# SCH_R2D2_2024-01-11.net
KiCad netlist of a schematic drawn in EasyEDA
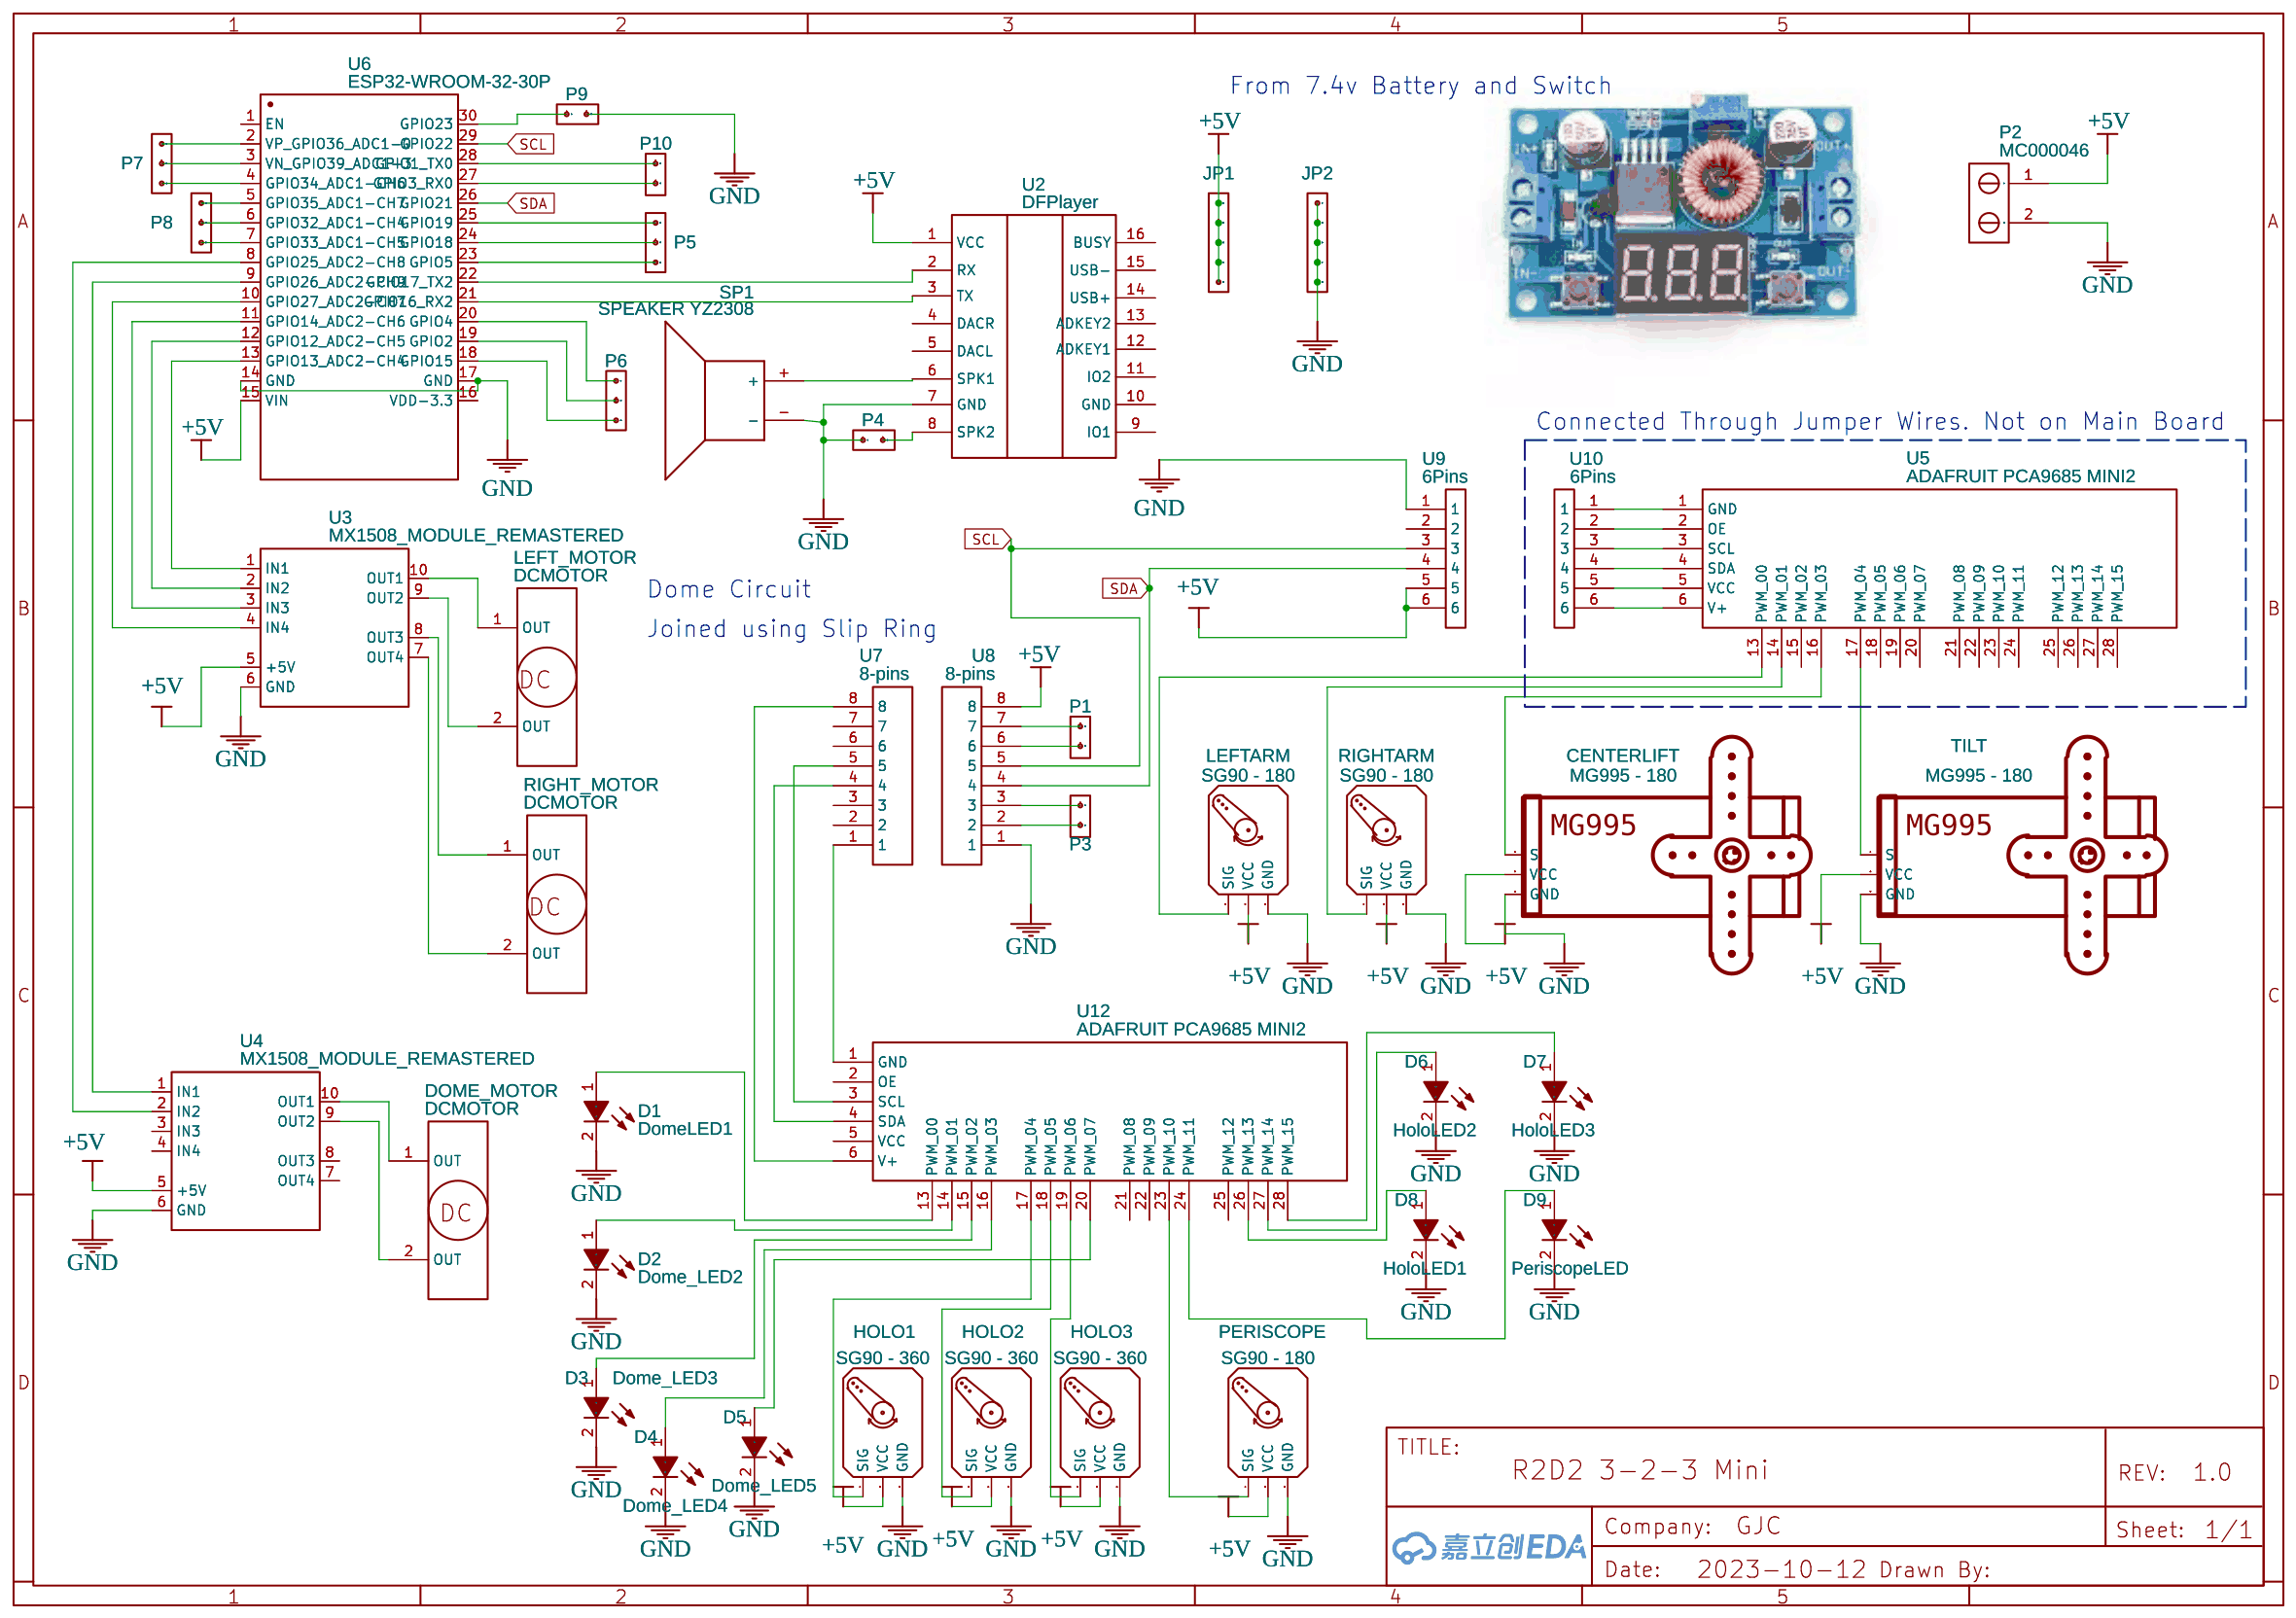
[diagram p0: schematic sheet]

(export (version "E")
  (design (tool "Eeschema 10.0.6"))
  (components
    (comp (ref "CENTERLIFT") (value "MG995 - 180") (libsource (lib "") (part "Servomotor_MG995_1")))
    (comp (ref "D1")
      (value "DomeLED1")
      (fields (field (name "Manufacturer Part") "5600") (field (name "Manufacturer") "VccLite"))
      (libsource (lib "") (part "3mm Green TH LED 5600"))
    )
    (comp (ref "D2")
      (value "Dome_LED2")
      (fields (field (name "Manufacturer Part") "5600") (field (name "Manufacturer") "VccLite"))
      (libsource (lib "") (part "3mm Green TH LED 5600"))
    )
    (comp (ref "D3")
      (value "Dome_LED3")
      (fields (field (name "Manufacturer Part") "5600") (field (name "Manufacturer") "VccLite"))
      (libsource (lib "") (part "3mm Green TH LED 5600"))
    )
    (comp (ref "D4")
      (value "Dome_LED4")
      (fields (field (name "Manufacturer Part") "5600") (field (name "Manufacturer") "VccLite"))
      (libsource (lib "") (part "3mm Green TH LED 5600"))
    )
    (comp (ref "D5")
      (value "Dome_LED5")
      (fields (field (name "Manufacturer Part") "5600") (field (name "Manufacturer") "VccLite"))
      (libsource (lib "") (part "3mm Green TH LED 5600"))
    )
    (comp (ref "D6")
      (value "HoloLED2")
      (fields (field (name "Manufacturer Part") "5600") (field (name "Manufacturer") "VccLite"))
      (libsource (lib "") (part "3mm Green TH LED 5600"))
    )
    (comp (ref "D7")
      (value "HoloLED3")
      (fields (field (name "Manufacturer Part") "5600") (field (name "Manufacturer") "VccLite"))
      (libsource (lib "") (part "3mm Green TH LED 5600"))
    )
    (comp (ref "D8")
      (value "HoloLED1")
      (fields (field (name "Manufacturer Part") "5600") (field (name "Manufacturer") "VccLite"))
      (libsource (lib "") (part "3mm Green TH LED 5600"))
    )
    (comp (ref "D9")
      (value "PeriscopeLED")
      (fields (field (name "Manufacturer Part") "5600") (field (name "Manufacturer") "VccLite"))
      (libsource (lib "") (part "3mm Green TH LED 5600"))
    )
    (comp (ref "DOME_MOTOR") (value "DCMOTOR") (libsource (lib "") (part "DCMOTOR_2")))
    (comp (ref "HOLO1") (value "SG90 - 360") (libsource (lib "") (part "SG90_Servo")))
    (comp (ref "HOLO2") (value "SG90 - 360") (libsource (lib "") (part "SG90_Servo")))
    (comp (ref "HOLO3") (value "SG90 - 360") (libsource (lib "") (part "SG90_Servo")))
    (comp (ref "JP1") (value "1X5PIN") (libsource (lib "") (part "1X5PIN")))
    (comp (ref "JP2") (value "1X5PIN") (libsource (lib "") (part "1X5PIN")))
    (comp (ref "LEFTARM") (value "SG90 - 180") (libsource (lib "") (part "SG90_Servo_2")))
    (comp (ref "LEFT_MOTOR") (value "DCMOTOR") (libsource (lib "") (part "DCMOTOR_1")))
    (comp (ref "P1") (value "1X2PIN") (libsource (lib "") (part "1X2PIN")))
    (comp (ref "P2")
      (value "MC000046")
      (fields (field (name "BOM_Supplier Part") "2008017"))
      (libsource (lib "") (part "MC000046"))
    )
    (comp (ref "P3") (value "1X2PIN") (libsource (lib "") (part "1X2PIN")))
    (comp (ref "P4") (value "1X2PIN") (libsource (lib "") (part "1X2PIN_1")))
    (comp (ref "P5") (value "1X3PIN") (libsource (lib "") (part "1X3PIN")))
    (comp (ref "P6") (value "1X3PIN") (libsource (lib "") (part "1X3PIN")))
    (comp (ref "P7") (value "1X3PIN") (libsource (lib "") (part "1X3PIN")))
    (comp (ref "P8") (value "1X3PIN") (libsource (lib "") (part "1X3PIN")))
    (comp (ref "P9") (value "1X2PIN") (libsource (lib "") (part "1X2PIN_1")))
    (comp (ref "P10") (value "1X2PIN") (libsource (lib "") (part "1X2PIN")))
    (comp (ref "PERISCOPE") (value "SG90 - 180") (libsource (lib "") (part "SG90_Servo_3")))
    (comp (ref "RIGHTARM") (value "SG90 - 180") (libsource (lib "") (part "SG90_Servo_1")))
    (comp (ref "RIGHT_MOTOR") (value "DCMOTOR") (libsource (lib "") (part "DCMOTOR")))
    (comp (ref "SP1")
      (value "SPEAKER YZ2308")
      (fields (field (name "BOM_Manufacturer Part") "YZ2308"))
      (libsource (lib "") (part "SPEAKER YZ2308"))
    )
    (comp (ref "TILT") (value "MG995 - 180") (libsource (lib "") (part "Servomotor_MG995")))
    (comp (ref "U2") (value "DFPlayer") (libsource (lib "") (part "DFPlayer")))
    (comp (ref "U3")
      (value "MX1508_MODULE_REMASTERED")
      (libsource (lib "") (part "MX1508_MODULE_REMASTERED"))
    )
    (comp (ref "U4")
      (value "MX1508_MODULE_REMASTERED")
      (libsource (lib "") (part "MX1508_MODULE_REMASTERED"))
    )
    (comp (ref "U5") (value "ADAFRUIT PCA9685 MINI2") (libsource (lib "") (part "ADAFRUIT PCA9685 MINI2")))
    (comp (ref "U6")
      (value "ESP32-WROOM-32-30P")
      (fields (field (name "BOM_Supplier Part") "C82899"))
      (libsource (lib "") (part "ESP32-WROOM-32-30P"))
    )
    (comp (ref "U7") (value "8-pins") (libsource (lib "") (part "8-pins_1")))
    (comp (ref "U8") (value "8-pins") (libsource (lib "") (part "8-pins")))
    (comp (ref "U9") (value "6Pins") (libsource (lib "") (part "6Pins_1")))
    (comp (ref "U10") (value "6Pins") (libsource (lib "") (part "6Pins")))
    (comp (ref "U12") (value "ADAFRUIT PCA9685 MINI2") (libsource (lib "") (part "ADAFRUIT PCA9685 MINI2")))
  )
  (nets
    (net (code "1") (name "+5V") (class "Default")
      (node (ref "CENTERLIFT") (pin "2") (pinfunction "VCC_2") (pintype "unspecified"))
      (node (ref "HOLO1") (pin "2") (pinfunction "VCC_2") (pintype "unspecified"))
      (node (ref "HOLO2") (pin "2") (pinfunction "VCC_2") (pintype "unspecified"))
      (node (ref "HOLO3") (pin "2") (pinfunction "VCC_2") (pintype "unspecified"))
      (node (ref "JP1") (pin "1") (pinfunction "1_1") (pintype "unspecified"))
      (node (ref "JP1") (pin "2") (pinfunction "2_2") (pintype "unspecified"))
      (node (ref "JP1") (pin "3") (pinfunction "3_3") (pintype "unspecified"))
      (node (ref "JP1") (pin "4") (pinfunction "4_4") (pintype "unspecified"))
      (node (ref "JP1") (pin "5") (pinfunction "5_5") (pintype "unspecified"))
      (node (ref "LEFTARM") (pin "2") (pinfunction "VCC_2") (pintype "unspecified"))
      (node (ref "P2") (pin "1") (pinfunction "1_1") (pintype "input"))
      (node (ref "PERISCOPE") (pin "2") (pinfunction "VCC_2") (pintype "unspecified"))
      (node (ref "RIGHTARM") (pin "2") (pinfunction "VCC_2") (pintype "unspecified"))
      (node (ref "TILT") (pin "2") (pinfunction "VCC_2") (pintype "unspecified"))
      (node (ref "U2") (pin "1") (pinfunction "VCC_1") (pintype "unspecified"))
      (node (ref "U3") (pin "5") (pinfunction "+5V_5") (pintype "unspecified"))
      (node (ref "U4") (pin "5") (pinfunction "+5V_5") (pintype "unspecified"))
      (node (ref "U6") (pin "15") (pinfunction "VIN_15") (pintype "unspecified"))
      (node (ref "U8") (pin "8") (pinfunction "8_8") (pintype "unspecified"))
      (node (ref "U9") (pin "5") (pinfunction "5_5") (pintype "unspecified"))
      (node (ref "U9") (pin "6") (pinfunction "6_6") (pintype "unspecified"))
    )
    (net (code "2") (name "GND") (class "Default")
      (node (ref "CENTERLIFT") (pin "3") (pinfunction "GND_3") (pintype "unspecified"))
      (node (ref "D1") (pin "2") (pinfunction "K_2") (pintype "unspecified"))
      (node (ref "D2") (pin "2") (pinfunction "K_2") (pintype "unspecified"))
      (node (ref "D3") (pin "2") (pinfunction "K_2") (pintype "unspecified"))
      (node (ref "D4") (pin "2") (pinfunction "K_2") (pintype "unspecified"))
      (node (ref "D5") (pin "2") (pinfunction "K_2") (pintype "unspecified"))
      (node (ref "D6") (pin "2") (pinfunction "K_2") (pintype "unspecified"))
      (node (ref "D7") (pin "2") (pinfunction "K_2") (pintype "unspecified"))
      (node (ref "D8") (pin "2") (pinfunction "K_2") (pintype "unspecified"))
      (node (ref "D9") (pin "2") (pinfunction "K_2") (pintype "unspecified"))
      (node (ref "HOLO1") (pin "3") (pinfunction "GND_3") (pintype "unspecified"))
      (node (ref "HOLO2") (pin "3") (pinfunction "GND_3") (pintype "unspecified"))
      (node (ref "HOLO3") (pin "3") (pinfunction "GND_3") (pintype "unspecified"))
      (node (ref "JP2") (pin "1") (pinfunction "1_1") (pintype "unspecified"))
      (node (ref "JP2") (pin "2") (pinfunction "2_2") (pintype "unspecified"))
      (node (ref "JP2") (pin "3") (pinfunction "3_3") (pintype "unspecified"))
      (node (ref "JP2") (pin "4") (pinfunction "4_4") (pintype "unspecified"))
      (node (ref "JP2") (pin "5") (pinfunction "5_5") (pintype "unspecified"))
      (node (ref "LEFTARM") (pin "3") (pinfunction "GND_3") (pintype "unspecified"))
      (node (ref "P2") (pin "2") (pinfunction "2_2") (pintype "input"))
      (node (ref "P4") (pin "1") (pinfunction "1_1") (pintype "unspecified"))
      (node (ref "P9") (pin "2") (pinfunction "2_2") (pintype "unspecified"))
      (node (ref "PERISCOPE") (pin "3") (pinfunction "GND_3") (pintype "unspecified"))
      (node (ref "RIGHTARM") (pin "3") (pinfunction "GND_3") (pintype "unspecified"))
      (node (ref "SP1") (pin "-") (pinfunction "-_-") (pintype "unspecified"))
      (node (ref "TILT") (pin "3") (pinfunction "GND_3") (pintype "unspecified"))
      (node (ref "U2") (pin "7") (pinfunction "GND_7") (pintype "unspecified"))
      (node (ref "U3") (pin "6") (pinfunction "GND_6") (pintype "unspecified"))
      (node (ref "U4") (pin "6") (pinfunction "GND_6") (pintype "unspecified"))
      (node (ref "U6") (pin "14") (pinfunction "GND_14") (pintype "unspecified"))
      (node (ref "U6") (pin "17") (pinfunction "GND_17") (pintype "unspecified"))
      (node (ref "U8") (pin "1") (pinfunction "1_1") (pintype "unspecified"))
      (node (ref "U9") (pin "1") (pinfunction "1_1") (pintype "unspecified"))
    )
    (net (code "3") (name "Net-(CENTERLIFT-S)") (class "Default")
      (node (ref "CENTERLIFT") (pin "1") (pinfunction "S_1") (pintype "unspecified"))
      (node (ref "U5") (pin "16") (pinfunction "PWM_03_16") (pintype "unspecified"))
    )
    (net (code "4") (name "Net-(D1-A)") (class "Default")
      (node (ref "D1") (pin "1") (pinfunction "A_1") (pintype "unspecified"))
      (node (ref "U12") (pin "13") (pinfunction "PWM_00_13") (pintype "unspecified"))
    )
    (net (code "5") (name "Net-(D2-A)") (class "Default")
      (node (ref "D2") (pin "1") (pinfunction "A_1") (pintype "unspecified"))
      (node (ref "U12") (pin "14") (pinfunction "PWM_01_14") (pintype "unspecified"))
    )
    (net (code "6") (name "Net-(D3-A)") (class "Default")
      (node (ref "D3") (pin "1") (pinfunction "A_1") (pintype "unspecified"))
      (node (ref "U12") (pin "15") (pinfunction "PWM_02_15") (pintype "unspecified"))
    )
    (net (code "7") (name "Net-(D4-A)") (class "Default")
      (node (ref "D4") (pin "1") (pinfunction "A_1") (pintype "unspecified"))
      (node (ref "U12") (pin "16") (pinfunction "PWM_03_16") (pintype "unspecified"))
    )
    (net (code "8") (name "Net-(D5-A)") (class "Default")
      (node (ref "D5") (pin "1") (pinfunction "A_1") (pintype "unspecified"))
      (node (ref "U12") (pin "20") (pinfunction "PWM_07_20") (pintype "unspecified"))
    )
    (net (code "9") (name "Net-(D6-A)") (class "Default")
      (node (ref "D6") (pin "1") (pinfunction "A_1") (pintype "unspecified"))
      (node (ref "U12") (pin "27") (pinfunction "PWM_14_27") (pintype "unspecified"))
    )
    (net (code "10") (name "Net-(D7-A)") (class "Default")
      (node (ref "D7") (pin "1") (pinfunction "A_1") (pintype "unspecified"))
      (node (ref "U12") (pin "28") (pinfunction "PWM_15_28") (pintype "unspecified"))
    )
    (net (code "11") (name "Net-(D8-A)") (class "Default")
      (node (ref "D8") (pin "1") (pinfunction "A_1") (pintype "unspecified"))
      (node (ref "U12") (pin "26") (pinfunction "PWM_13_26") (pintype "unspecified"))
    )
    (net (code "12") (name "Net-(D9-A)") (class "Default")
      (node (ref "D9") (pin "1") (pinfunction "A_1") (pintype "unspecified"))
      (node (ref "U12") (pin "24") (pinfunction "PWM_11_24") (pintype "unspecified"))
    )
    (net (code "13") (name "Net-(HOLO1-SIG)") (class "Default")
      (node (ref "HOLO1") (pin "1") (pinfunction "SIG_1") (pintype "unspecified"))
      (node (ref "U12") (pin "17") (pinfunction "PWM_04_17") (pintype "unspecified"))
    )
    (net (code "14") (name "Net-(HOLO2-SIG)") (class "Default")
      (node (ref "HOLO2") (pin "1") (pinfunction "SIG_1") (pintype "unspecified"))
      (node (ref "U12") (pin "18") (pinfunction "PWM_05_18") (pintype "unspecified"))
    )
    (net (code "15") (name "Net-(HOLO3-SIG)") (class "Default")
      (node (ref "HOLO3") (pin "1") (pinfunction "SIG_1") (pintype "unspecified"))
      (node (ref "U12") (pin "19") (pinfunction "PWM_06_19") (pintype "unspecified"))
    )
    (net (code "16") (name "Net-(LEFTARM-SIG)") (class "Default")
      (node (ref "LEFTARM") (pin "1") (pinfunction "SIG_1") (pintype "unspecified"))
      (node (ref "U5") (pin "13") (pinfunction "PWM_00_13") (pintype "unspecified"))
    )
    (net (code "17") (name "Net-(P1-Pad1)") (class "Default")
      (node (ref "P1") (pin "1") (pinfunction "1_1") (pintype "unspecified"))
      (node (ref "U8") (pin "7") (pinfunction "7_7") (pintype "unspecified"))
    )
    (net (code "18") (name "Net-(P1-Pad2)") (class "Default")
      (node (ref "P1") (pin "2") (pinfunction "2_2") (pintype "unspecified"))
      (node (ref "U8") (pin "6") (pinfunction "6_6") (pintype "unspecified"))
    )
    (net (code "19") (name "Net-(P3-Pad1)") (class "Default")
      (node (ref "P3") (pin "1") (pinfunction "1_1") (pintype "unspecified"))
      (node (ref "U8") (pin "3") (pinfunction "3_3") (pintype "unspecified"))
    )
    (net (code "20") (name "Net-(P3-Pad2)") (class "Default")
      (node (ref "P3") (pin "2") (pinfunction "2_2") (pintype "unspecified"))
      (node (ref "U8") (pin "2") (pinfunction "2_2") (pintype "unspecified"))
    )
    (net (code "21") (name "Net-(PERISCOPE-SIG)") (class "Default")
      (node (ref "PERISCOPE") (pin "1") (pinfunction "SIG_1") (pintype "unspecified"))
      (node (ref "U12") (pin "23") (pinfunction "PWM_10_23") (pintype "unspecified"))
    )
    (net (code "22") (name "Net-(RIGHTARM-SIG)") (class "Default")
      (node (ref "RIGHTARM") (pin "1") (pinfunction "SIG_1") (pintype "unspecified"))
      (node (ref "U5") (pin "14") (pinfunction "PWM_01_14") (pintype "unspecified"))
    )
    (net (code "23") (name "Net-(TILT-S)") (class "Default")
      (node (ref "TILT") (pin "1") (pinfunction "S_1") (pintype "unspecified"))
      (node (ref "U5") (pin "17") (pinfunction "PWM_04_17") (pintype "unspecified"))
    )
    (net (code "24") (name "Net-(U2-RX)") (class "Default")
      (node (ref "U2") (pin "2") (pinfunction "RX_2") (pintype "unspecified"))
      (node (ref "U6") (pin "22") (pinfunction "GPIO17_TX2_22") (pintype "unspecified"))
    )
    (net (code "25") (name "Net-(U2-SPK1)") (class "Default")
      (node (ref "SP1") (pin "+") (pinfunction "+_+") (pintype "unspecified"))
      (node (ref "U2") (pin "6") (pinfunction "SPK1_6") (pintype "unspecified"))
    )
    (net (code "26") (name "Net-(U2-SPK2)") (class "Default")
      (node (ref "P4") (pin "2") (pinfunction "2_2") (pintype "unspecified"))
      (node (ref "U2") (pin "8") (pinfunction "SPK2_8") (pintype "unspecified"))
    )
    (net (code "27") (name "Net-(U2-TX)") (class "Default")
      (node (ref "U2") (pin "3") (pinfunction "TX_3") (pintype "unspecified"))
      (node (ref "U6") (pin "21") (pinfunction "GPIO16_RX2_21") (pintype "unspecified"))
    )
    (net (code "28") (name "Net-(U3-IN1)") (class "Default")
      (node (ref "U3") (pin "1") (pinfunction "IN1_1") (pintype "unspecified"))
      (node (ref "U6") (pin "13") (pinfunction "GPIO13_ADC2-CH4_13") (pintype "unspecified"))
    )
    (net (code "29") (name "Net-(U3-IN2)") (class "Default")
      (node (ref "U3") (pin "2") (pinfunction "IN2_2") (pintype "unspecified"))
      (node (ref "U6") (pin "12") (pinfunction "GPIO12_ADC2-CH5_12") (pintype "unspecified"))
    )
    (net (code "30") (name "Net-(U3-IN3)") (class "Default")
      (node (ref "U3") (pin "3") (pinfunction "IN3_3") (pintype "unspecified"))
      (node (ref "U6") (pin "11") (pinfunction "GPIO14_ADC2-CH6_11") (pintype "unspecified"))
    )
    (net (code "31") (name "Net-(U3-IN4)") (class "Default")
      (node (ref "U3") (pin "4") (pinfunction "IN4_4") (pintype "unspecified"))
      (node (ref "U6") (pin "10") (pinfunction "GPIO27_ADC2-CH7_10") (pintype "unspecified"))
    )
    (net (code "32") (name "Net-(U3-OUT1)") (class "Default")
      (node (ref "LEFT_MOTOR") (pin "1") (pinfunction "OUT_1") (pintype "unspecified"))
      (node (ref "U3") (pin "10") (pinfunction "OUT1_10") (pintype "unspecified"))
    )
    (net (code "33") (name "Net-(U3-OUT2)") (class "Default")
      (node (ref "LEFT_MOTOR") (pin "2") (pinfunction "OUT_2") (pintype "unspecified"))
      (node (ref "U3") (pin "9") (pinfunction "OUT2_9") (pintype "unspecified"))
    )
    (net (code "34") (name "Net-(U3-OUT3)") (class "Default")
      (node (ref "RIGHT_MOTOR") (pin "1") (pinfunction "OUT_1") (pintype "unspecified"))
      (node (ref "U3") (pin "8") (pinfunction "OUT3_8") (pintype "unspecified"))
    )
    (net (code "35") (name "Net-(U3-OUT4)") (class "Default")
      (node (ref "RIGHT_MOTOR") (pin "2") (pinfunction "OUT_2") (pintype "unspecified"))
      (node (ref "U3") (pin "7") (pinfunction "OUT4_7") (pintype "unspecified"))
    )
    (net (code "36") (name "Net-(U4-IN1)") (class "Default")
      (node (ref "U4") (pin "1") (pinfunction "IN1_1") (pintype "unspecified"))
      (node (ref "U6") (pin "9") (pinfunction "GPIO26_ADC2-CH9_9") (pintype "unspecified"))
    )
    (net (code "37") (name "Net-(U4-IN2)") (class "Default")
      (node (ref "U4") (pin "2") (pinfunction "IN2_2") (pintype "unspecified"))
      (node (ref "U6") (pin "8") (pinfunction "GPIO25_ADC2-CH8_8") (pintype "unspecified"))
    )
    (net (code "38") (name "Net-(U4-OUT1)") (class "Default")
      (node (ref "DOME_MOTOR") (pin "1") (pinfunction "OUT_1") (pintype "unspecified"))
      (node (ref "U4") (pin "10") (pinfunction "OUT1_10") (pintype "unspecified"))
    )
    (net (code "39") (name "Net-(U4-OUT2)") (class "Default")
      (node (ref "DOME_MOTOR") (pin "2") (pinfunction "OUT_2") (pintype "unspecified"))
      (node (ref "U4") (pin "9") (pinfunction "OUT2_9") (pintype "unspecified"))
    )
    (net (code "40") (name "Net-(U5-GND)") (class "Default")
      (node (ref "U10") (pin "1") (pinfunction "1_1") (pintype "unspecified"))
      (node (ref "U5") (pin "1") (pinfunction "GND_1") (pintype "unspecified"))
    )
    (net (code "41") (name "Net-(U5-OE)") (class "Default")
      (node (ref "U10") (pin "2") (pinfunction "2_2") (pintype "unspecified"))
      (node (ref "U5") (pin "2") (pinfunction "OE_2") (pintype "unspecified"))
    )
    (net (code "42") (name "Net-(U5-SCL)") (class "Default")
      (node (ref "U10") (pin "3") (pinfunction "3_3") (pintype "unspecified"))
      (node (ref "U5") (pin "3") (pinfunction "SCL_3") (pintype "unspecified"))
    )
    (net (code "43") (name "Net-(U5-SDA)") (class "Default")
      (node (ref "U10") (pin "4") (pinfunction "4_4") (pintype "unspecified"))
      (node (ref "U5") (pin "4") (pinfunction "SDA_4") (pintype "unspecified"))
    )
    (net (code "44") (name "Net-(U5-V+)") (class "Default")
      (node (ref "U10") (pin "6") (pinfunction "6_6") (pintype "unspecified"))
      (node (ref "U5") (pin "6") (pinfunction "V+_6") (pintype "unspecified"))
    )
    (net (code "45") (name "Net-(U5-VCC)") (class "Default")
      (node (ref "U10") (pin "5") (pinfunction "5_5") (pintype "unspecified"))
      (node (ref "U5") (pin "5") (pinfunction "VCC_5") (pintype "unspecified"))
    )
    (net (code "46") (name "Net-(U6-GPIO1_TX0)") (class "Default")
      (node (ref "P10") (pin "1") (pinfunction "1_1") (pintype "unspecified"))
      (node (ref "U6") (pin "28") (pinfunction "GPIO1_TX0_28") (pintype "unspecified"))
    )
    (net (code "47") (name "Net-(U6-GPIO2)") (class "Default")
      (node (ref "P6") (pin "2") (pinfunction "2_2") (pintype "unspecified"))
      (node (ref "U6") (pin "19") (pinfunction "GPIO2_19") (pintype "unspecified"))
    )
    (net (code "48") (name "Net-(U6-GPIO3_RX0)") (class "Default")
      (node (ref "P10") (pin "2") (pinfunction "2_2") (pintype "unspecified"))
      (node (ref "U6") (pin "27") (pinfunction "GPIO3_RX0_27") (pintype "unspecified"))
    )
    (net (code "49") (name "Net-(U6-GPIO4)") (class "Default")
      (node (ref "P6") (pin "1") (pinfunction "1_1") (pintype "unspecified"))
      (node (ref "U6") (pin "20") (pinfunction "GPIO4_20") (pintype "unspecified"))
    )
    (net (code "50") (name "Net-(U6-GPIO5)") (class "Default")
      (node (ref "P5") (pin "3") (pinfunction "3_3") (pintype "unspecified"))
      (node (ref "U6") (pin "23") (pinfunction "GPIO5_23") (pintype "unspecified"))
    )
    (net (code "51") (name "Net-(U6-GPIO15)") (class "Default")
      (node (ref "P6") (pin "3") (pinfunction "3_3") (pintype "unspecified"))
      (node (ref "U6") (pin "18") (pinfunction "GPIO15_18") (pintype "unspecified"))
    )
    (net (code "52") (name "Net-(U6-GPIO18)") (class "Default")
      (node (ref "P5") (pin "2") (pinfunction "2_2") (pintype "unspecified"))
      (node (ref "U6") (pin "24") (pinfunction "GPIO18_24") (pintype "unspecified"))
    )
    (net (code "53") (name "Net-(U6-GPIO19)") (class "Default")
      (node (ref "P5") (pin "1") (pinfunction "1_1") (pintype "unspecified"))
      (node (ref "U6") (pin "25") (pinfunction "GPIO19_25") (pintype "unspecified"))
    )
    (net (code "54") (name "Net-(U6-GPIO23)") (class "Default")
      (node (ref "P9") (pin "1") (pinfunction "1_1") (pintype "unspecified"))
      (node (ref "U6") (pin "30") (pinfunction "GPIO23_30") (pintype "unspecified"))
    )
    (net (code "55") (name "Net-(U6-GPIO32_ADC1-CH4)") (class "Default")
      (node (ref "P8") (pin "2") (pinfunction "2_2") (pintype "unspecified"))
      (node (ref "U6") (pin "6") (pinfunction "GPIO32_ADC1-CH4_6") (pintype "unspecified"))
    )
    (net (code "56") (name "Net-(U6-GPIO33_ADC1-CH5)") (class "Default")
      (node (ref "P8") (pin "3") (pinfunction "3_3") (pintype "unspecified"))
      (node (ref "U6") (pin "7") (pinfunction "GPIO33_ADC1-CH5_7") (pintype "unspecified"))
    )
    (net (code "57") (name "Net-(U6-GPIO34_ADC1-CH6)") (class "Default")
      (node (ref "P7") (pin "3") (pinfunction "3_3") (pintype "unspecified"))
      (node (ref "U6") (pin "4") (pinfunction "GPIO34_ADC1-CH6_4") (pintype "unspecified"))
    )
    (net (code "58") (name "Net-(U6-GPIO35_ADC1-CH7)") (class "Default")
      (node (ref "P8") (pin "1") (pinfunction "1_1") (pintype "unspecified"))
      (node (ref "U6") (pin "5") (pinfunction "GPIO35_ADC1-CH7_5") (pintype "unspecified"))
    )
    (net (code "59") (name "Net-(U6-VN_GPIO39_ADC1-3)") (class "Default")
      (node (ref "P7") (pin "2") (pinfunction "2_2") (pintype "unspecified"))
      (node (ref "U6") (pin "3") (pinfunction "VN_GPIO39_ADC1-3_3") (pintype "unspecified"))
    )
    (net (code "60") (name "Net-(U6-VP_GPIO36_ADC1-0)") (class "Default")
      (node (ref "P7") (pin "1") (pinfunction "1_1") (pintype "unspecified"))
      (node (ref "U6") (pin "2") (pinfunction "VP_GPIO36_ADC1-0_2") (pintype "unspecified"))
    )
    (net (code "61") (name "Net-(U12-GND)") (class "Default")
      (node (ref "U12") (pin "1") (pinfunction "GND_1") (pintype "unspecified"))
      (node (ref "U7") (pin "1") (pinfunction "1_1") (pintype "unspecified"))
    )
    (net (code "62") (name "Net-(U12-SCL)") (class "Default")
      (node (ref "U12") (pin "3") (pinfunction "SCL_3") (pintype "unspecified"))
      (node (ref "U7") (pin "5") (pinfunction "5_5") (pintype "unspecified"))
    )
    (net (code "63") (name "Net-(U12-SDA)") (class "Default")
      (node (ref "U12") (pin "4") (pinfunction "SDA_4") (pintype "unspecified"))
      (node (ref "U7") (pin "4") (pinfunction "4_4") (pintype "unspecified"))
    )
    (net (code "64") (name "Net-(U12-V+)") (class "Default")
      (node (ref "U12") (pin "6") (pinfunction "V+_6") (pintype "unspecified"))
      (node (ref "U7") (pin "8") (pinfunction "8_8") (pintype "unspecified"))
    )
    (net (code "65") (name "SCL") (class "Default")
      (node (ref "U6") (pin "29") (pinfunction "GPIO22_29") (pintype "unspecified"))
      (node (ref "U8") (pin "5") (pinfunction "5_5") (pintype "unspecified"))
      (node (ref "U9") (pin "3") (pinfunction "3_3") (pintype "unspecified"))
    )
    (net (code "66") (name "SDA") (class "Default")
      (node (ref "U6") (pin "26") (pinfunction "GPIO21_26") (pintype "unspecified"))
      (node (ref "U8") (pin "4") (pinfunction "4_4") (pintype "unspecified"))
      (node (ref "U9") (pin "4") (pinfunction "4_4") (pintype "unspecified"))
    )
    (net (code "67") (name "unconnected-(U2-ADKEY1-Pad12)") (class "Default")
      (node (ref "U2") (pin "12") (pinfunction "ADKEY1_12") (pintype "unspecified"))
    )
    (net (code "68") (name "unconnected-(U2-ADKEY2-Pad13)") (class "Default")
      (node (ref "U2") (pin "13") (pinfunction "ADKEY2_13") (pintype "unspecified"))
    )
    (net (code "69") (name "unconnected-(U2-BUSY-Pad16)") (class "Default")
      (node (ref "U2") (pin "16") (pinfunction "BUSY_16") (pintype "unspecified"))
    )
    (net (code "70") (name "unconnected-(U2-DACL-Pad5)") (class "Default")
      (node (ref "U2") (pin "5") (pinfunction "DACL_5") (pintype "unspecified"))
    )
    (net (code "71") (name "unconnected-(U2-DACR-Pad4)") (class "Default")
      (node (ref "U2") (pin "4") (pinfunction "DACR_4") (pintype "unspecified"))
    )
    (net (code "72") (name "unconnected-(U2-GND-Pad10)") (class "Default")
      (node (ref "U2") (pin "10") (pinfunction "GND_10") (pintype "unspecified"))
    )
    (net (code "73") (name "unconnected-(U2-IO1-Pad9)") (class "Default")
      (node (ref "U2") (pin "9") (pinfunction "IO1_9") (pintype "unspecified"))
    )
    (net (code "74") (name "unconnected-(U2-IO2-Pad11)") (class "Default")
      (node (ref "U2") (pin "11") (pinfunction "IO2_11") (pintype "unspecified"))
    )
    (net (code "75") (name "unconnected-(U2-USB+-Pad14)") (class "Default")
      (node (ref "U2") (pin "14") (pinfunction "USB+_14") (pintype "unspecified"))
    )
    (net (code "76") (name "unconnected-(U2-USB--Pad15)") (class "Default")
      (node (ref "U2") (pin "15") (pinfunction "USB-_15") (pintype "unspecified"))
    )
    (net (code "77") (name "unconnected-(U4-IN3-Pad3)") (class "Default")
      (node (ref "U4") (pin "3") (pinfunction "IN3_3") (pintype "unspecified"))
    )
    (net (code "78") (name "unconnected-(U4-IN4-Pad4)") (class "Default")
      (node (ref "U4") (pin "4") (pinfunction "IN4_4") (pintype "unspecified"))
    )
    (net (code "79") (name "unconnected-(U4-OUT3-Pad8)") (class "Default")
      (node (ref "U4") (pin "8") (pinfunction "OUT3_8") (pintype "unspecified"))
    )
    (net (code "80") (name "unconnected-(U4-OUT4-Pad7)") (class "Default")
      (node (ref "U4") (pin "7") (pinfunction "OUT4_7") (pintype "unspecified"))
    )
    (net (code "81") (name "unconnected-(U5-PWM_02-Pad15)") (class "Default")
      (node (ref "U5") (pin "15") (pinfunction "PWM_02_15") (pintype "unspecified"))
    )
    (net (code "82") (name "unconnected-(U5-PWM_05-Pad18)") (class "Default")
      (node (ref "U5") (pin "18") (pinfunction "PWM_05_18") (pintype "unspecified"))
    )
    (net (code "83") (name "unconnected-(U5-PWM_06-Pad19)") (class "Default")
      (node (ref "U5") (pin "19") (pinfunction "PWM_06_19") (pintype "unspecified"))
    )
    (net (code "84") (name "unconnected-(U5-PWM_07-Pad20)") (class "Default")
      (node (ref "U5") (pin "20") (pinfunction "PWM_07_20") (pintype "unspecified"))
    )
    (net (code "85") (name "unconnected-(U5-PWM_08-Pad21)") (class "Default")
      (node (ref "U5") (pin "21") (pinfunction "PWM_08_21") (pintype "unspecified"))
    )
    (net (code "86") (name "unconnected-(U5-PWM_09-Pad22)") (class "Default")
      (node (ref "U5") (pin "22") (pinfunction "PWM_09_22") (pintype "unspecified"))
    )
    (net (code "87") (name "unconnected-(U5-PWM_10-Pad23)") (class "Default")
      (node (ref "U5") (pin "23") (pinfunction "PWM_10_23") (pintype "unspecified"))
    )
    (net (code "88") (name "unconnected-(U5-PWM_11-Pad24)") (class "Default")
      (node (ref "U5") (pin "24") (pinfunction "PWM_11_24") (pintype "unspecified"))
    )
    (net (code "89") (name "unconnected-(U5-PWM_12-Pad25)") (class "Default")
      (node (ref "U5") (pin "25") (pinfunction "PWM_12_25") (pintype "unspecified"))
    )
    (net (code "90") (name "unconnected-(U5-PWM_13-Pad26)") (class "Default")
      (node (ref "U5") (pin "26") (pinfunction "PWM_13_26") (pintype "unspecified"))
    )
    (net (code "91") (name "unconnected-(U5-PWM_14-Pad27)") (class "Default")
      (node (ref "U5") (pin "27") (pinfunction "PWM_14_27") (pintype "unspecified"))
    )
    (net (code "92") (name "unconnected-(U5-PWM_15-Pad28)") (class "Default")
      (node (ref "U5") (pin "28") (pinfunction "PWM_15_28") (pintype "unspecified"))
    )
    (net (code "93") (name "unconnected-(U6-EN-Pad1)") (class "Default")
      (node (ref "U6") (pin "1") (pinfunction "EN_1") (pintype "unspecified"))
    )
    (net (code "94") (name "unconnected-(U6-VDD-3.3-Pad16)") (class "Default")
      (node (ref "U6") (pin "16") (pinfunction "VDD-3.3_16") (pintype "unspecified"))
    )
    (net (code "95") (name "unconnected-(U7-Pad2)") (class "Default")
      (node (ref "U7") (pin "2") (pinfunction "2_2") (pintype "unspecified"))
    )
    (net (code "96") (name "unconnected-(U7-Pad3)") (class "Default")
      (node (ref "U7") (pin "3") (pinfunction "3_3") (pintype "unspecified"))
    )
    (net (code "97") (name "unconnected-(U7-Pad6)") (class "Default")
      (node (ref "U7") (pin "6") (pinfunction "6_6") (pintype "unspecified"))
    )
    (net (code "98") (name "unconnected-(U7-Pad7)") (class "Default")
      (node (ref "U7") (pin "7") (pinfunction "7_7") (pintype "unspecified"))
    )
    (net (code "99") (name "unconnected-(U9-Pad2)") (class "Default")
      (node (ref "U9") (pin "2") (pinfunction "2_2") (pintype "unspecified"))
    )
    (net (code "100") (name "unconnected-(U12-OE-Pad2)") (class "Default")
      (node (ref "U12") (pin "2") (pinfunction "OE_2") (pintype "unspecified"))
    )
    (net (code "101") (name "unconnected-(U12-PWM_08-Pad21)") (class "Default")
      (node (ref "U12") (pin "21") (pinfunction "PWM_08_21") (pintype "unspecified"))
    )
    (net (code "102") (name "unconnected-(U12-PWM_09-Pad22)") (class "Default")
      (node (ref "U12") (pin "22") (pinfunction "PWM_09_22") (pintype "unspecified"))
    )
    (net (code "103") (name "unconnected-(U12-PWM_12-Pad25)") (class "Default")
      (node (ref "U12") (pin "25") (pinfunction "PWM_12_25") (pintype "unspecified"))
    )
    (net (code "104") (name "unconnected-(U12-VCC-Pad5)") (class "Default")
      (node (ref "U12") (pin "5") (pinfunction "VCC_5") (pintype "unspecified"))
    )
  )
)
